# DC-DC_Isolation.net
KiCad netlist of a schematic drawn in Altium Designer
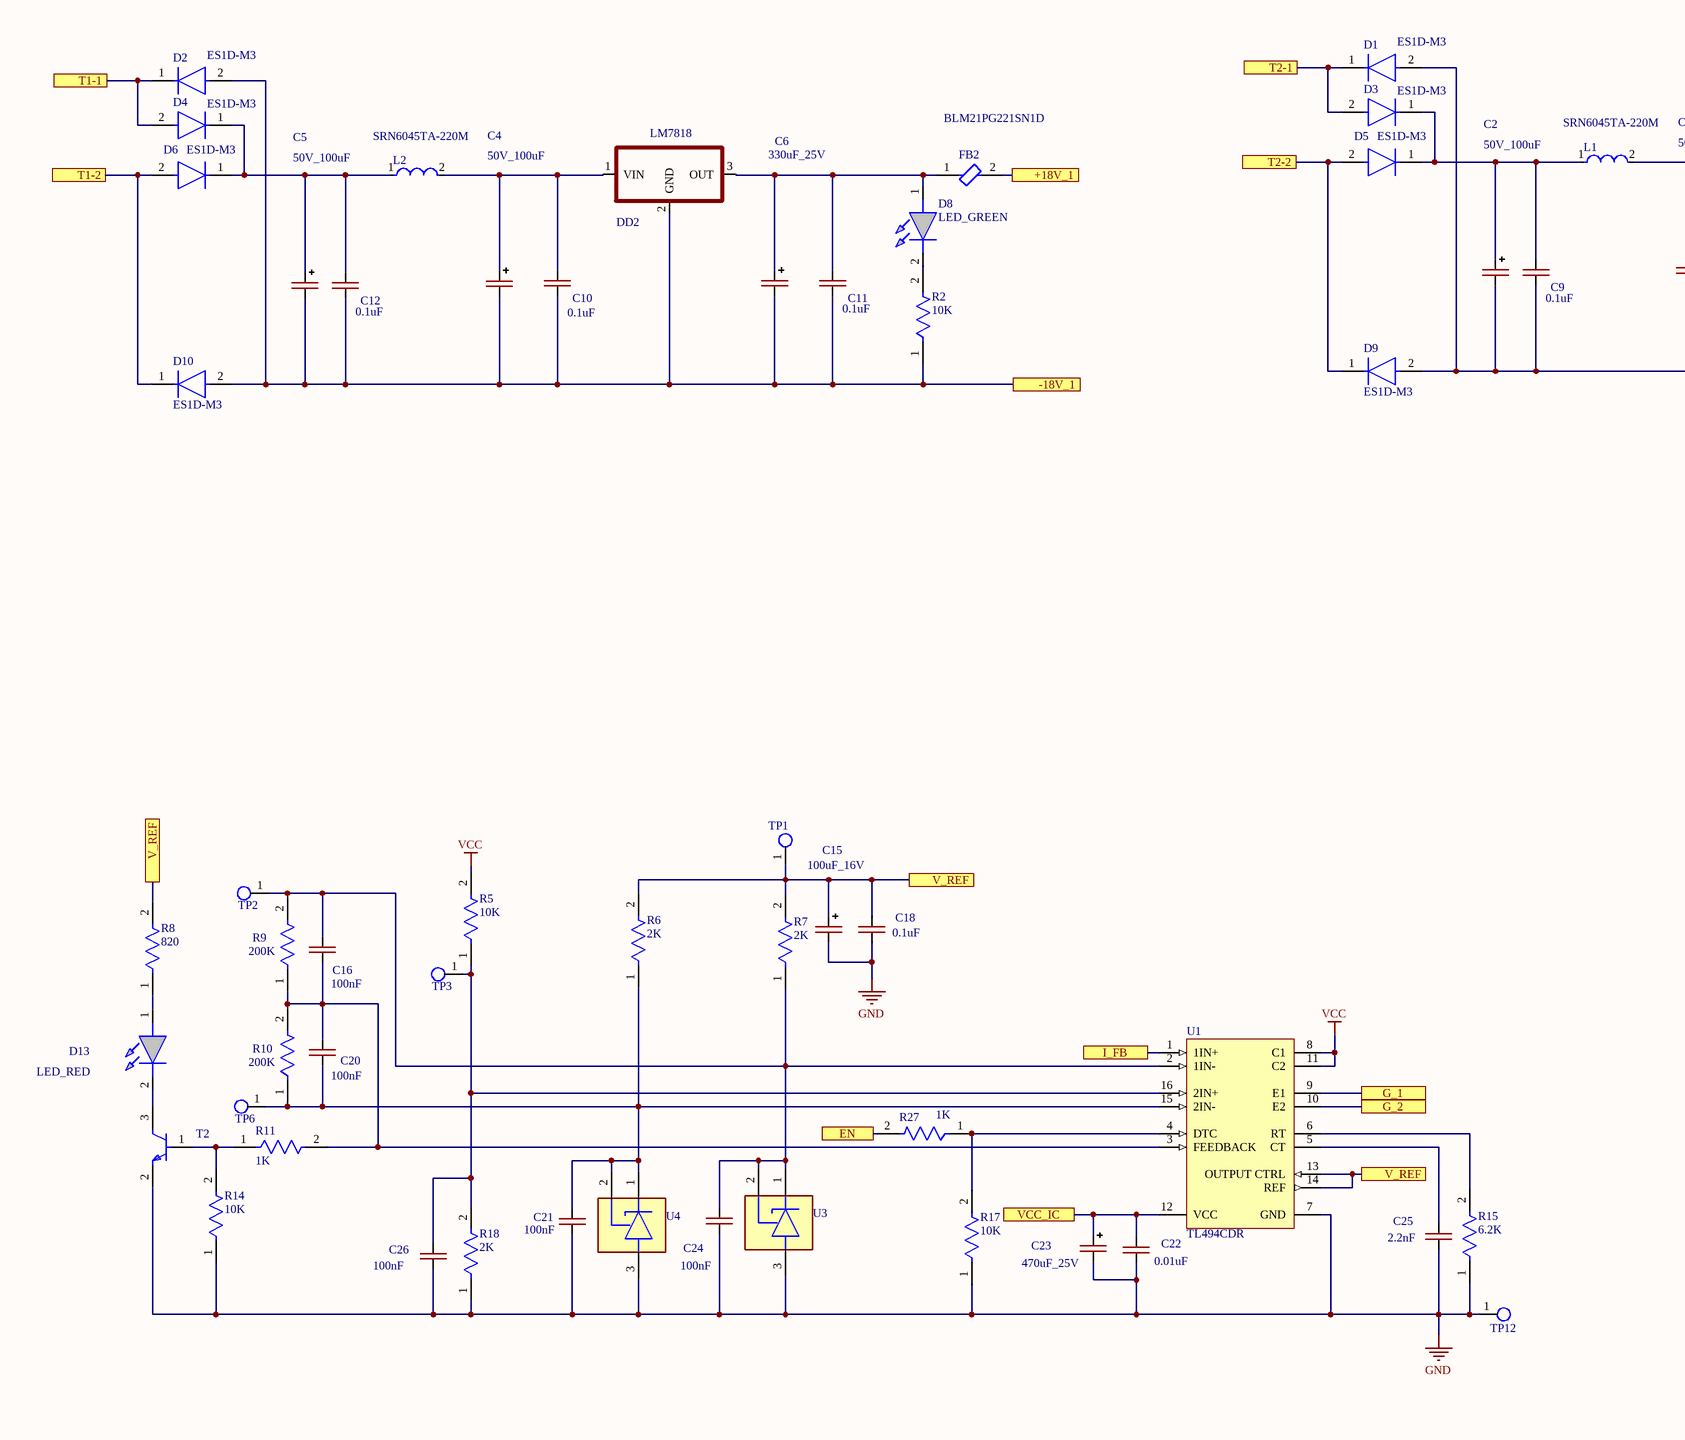
[diagram p0: DC-DC_Isolation.SchDoc, left]
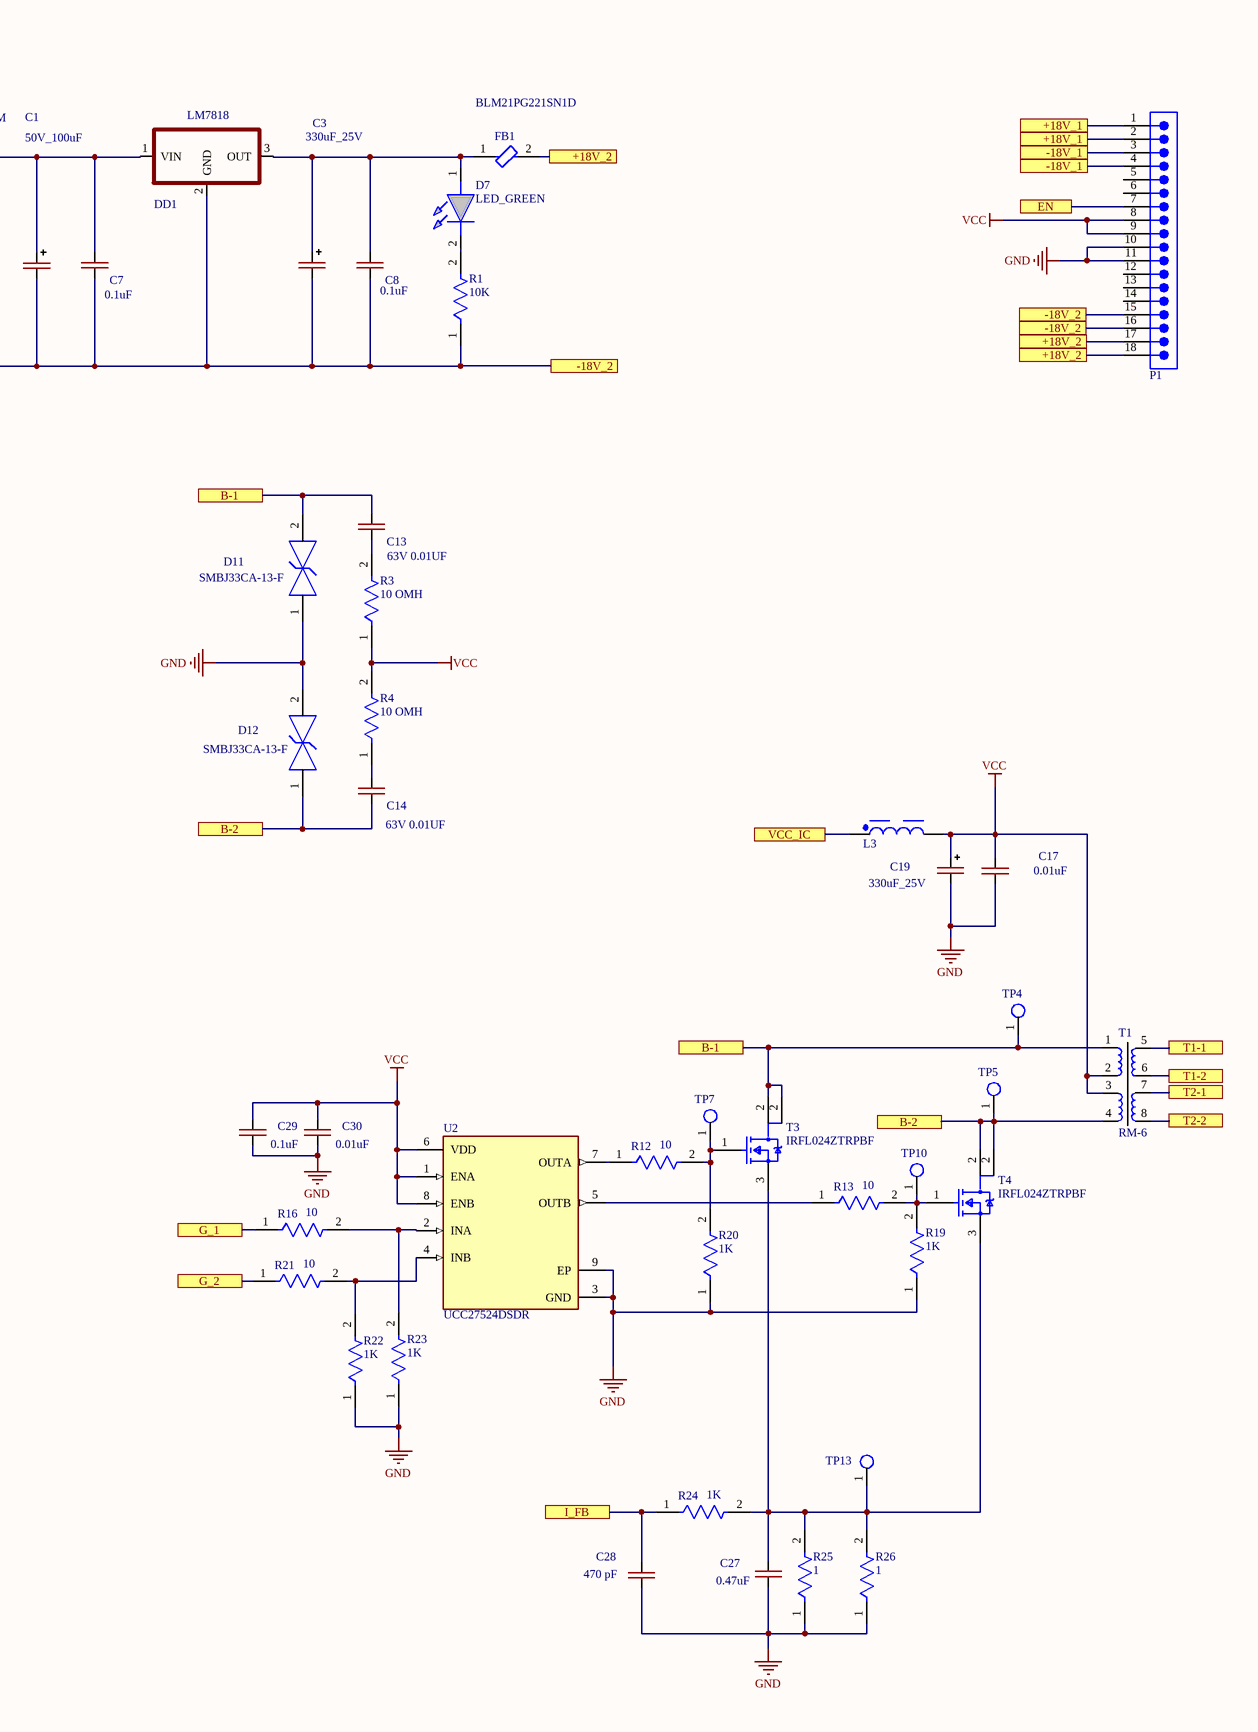
[diagram p1: DC-DC_Isolation.SchDoc, right]

(export (version "E")
  (design (tool "Eeschema 10.0.6"))
  (components
    (comp (ref "C1")
      (value "50V_100uF")
      (footprint "CAP_SMD_Size_G")
      (libsource (lib "PASSIVE_COMPONENTS") (part "CAP-POLAR"))
    )
    (comp (ref "C2")
      (value "50V_100uF")
      (footprint "CAP_SMD_Size_G")
      (libsource (lib "PASSIVE_COMPONENTS") (part "CAP-POLAR"))
    )
    (comp (ref "C3")
      (value "330uF_25V")
      (footprint "CAP_SMD_Size_G")
      (libsource (lib "PASSIVE_COMPONENTS") (part "CAP-POLAR"))
    )
    (comp (ref "C4")
      (value "50V_100uF")
      (footprint "CAP_SMD_Size_G")
      (libsource (lib "PASSIVE_COMPONENTS") (part "CAP-POLAR"))
    )
    (comp (ref "C5")
      (value "50V_100uF")
      (footprint "CAP_SMD_Size_G")
      (libsource (lib "PASSIVE_COMPONENTS") (part "CAP-POLAR"))
    )
    (comp (ref "C6")
      (value "330uF_25V")
      (footprint "CAP_SMD_Size_G")
      (libsource (lib "PASSIVE_COMPONENTS") (part "CAP-POLAR"))
    )
    (comp (ref "C7")
      (value "0.1uF")
      (footprint "CAP-0805")
      (description "0.1uF X7R")
      (libsource (lib "PASSIVE_COMPONENTS") (part "CAP-NON-POLAR"))
    )
    (comp (ref "C8")
      (value "0.1uF")
      (footprint "CAP-0805")
      (libsource (lib "PASSIVE_COMPONENTS") (part "CAP-NON-POLAR"))
    )
    (comp (ref "C9")
      (value "0.1uF")
      (footprint "CAP-0805")
      (description "0.1uF X7R")
      (libsource (lib "PASSIVE_COMPONENTS") (part "CAP-NON-POLAR"))
    )
    (comp (ref "C10")
      (value "0.1uF")
      (footprint "CAP-0805")
      (description "0.1uF X7R")
      (libsource (lib "PASSIVE_COMPONENTS") (part "CAP-NON-POLAR"))
    )
    (comp (ref "C11")
      (value "0.1uF")
      (footprint "CAP-0805")
      (libsource (lib "PASSIVE_COMPONENTS") (part "CAP-NON-POLAR"))
    )
    (comp (ref "C12")
      (value "0.1uF")
      (footprint "CAP-0805")
      (description "0.1uF X7R")
      (libsource (lib "PASSIVE_COMPONENTS") (part "CAP-NON-POLAR"))
    )
    (comp (ref "C13")
      (value "63V 0.01UF")
      (footprint "FKP2D011001A00JSSD")
      (description "WIMA Film Capacitor FKP2 63V 0.01UF")
      (libsource (lib "PASSIVE_COMPONENTS") (part "CAP-NON-POLAR"))
    )
    (comp (ref "C14")
      (value "63V 0.01UF")
      (footprint "FKP2D011001A00JSSD")
      (description "WIMA Film Capacitor FKP2 63V 0.01UF")
      (libsource (lib "PASSIVE_COMPONENTS") (part "CAP-NON-POLAR"))
    )
    (comp (ref "C15")
      (value "100uF_16V")
      (footprint "CAP-TAN-D")
      (libsource (lib "PASSIVE_COMPONENTS") (part "CAP-POLAR"))
    )
    (comp (ref "C16")
      (value "100nF")
      (footprint "CAP-0603")
      (libsource (lib "PASSIVE_COMPONENTS") (part "CAP-NON-POLAR"))
    )
    (comp (ref "C17")
      (value "0.01uF")
      (footprint "CAP-0805")
      (libsource (lib "PASSIVE_COMPONENTS") (part "CAP-NON-POLAR"))
    )
    (comp (ref "C18")
      (value "0.1uF")
      (footprint "CAP-0603")
      (libsource (lib "PASSIVE_COMPONENTS") (part "CAP-NON-POLAR"))
    )
    (comp (ref "C19")
      (value "330uF_25V")
      (footprint "CAP_SMD_Size_G")
      (libsource (lib "PASSIVE_COMPONENTS") (part "CAP-POLAR"))
    )
    (comp (ref "C20")
      (value "100nF")
      (footprint "CAP-0603")
      (libsource (lib "PASSIVE_COMPONENTS") (part "CAP-NON-POLAR"))
    )
    (comp (ref "C21")
      (value "100nF")
      (footprint "CAP-0603")
      (libsource (lib "PASSIVE_COMPONENTS") (part "CAP-NON-POLAR"))
    )
    (comp (ref "C22")
      (value "0.01uF")
      (footprint "CAP-0603")
      (libsource (lib "PASSIVE_COMPONENTS") (part "CAP-NON-POLAR"))
    )
    (comp (ref "C23")
      (value "470uF_25V")
      (footprint "CAP_SMD_Size_G")
      (libsource (lib "PASSIVE_COMPONENTS") (part "CAP-POLAR"))
    )
    (comp (ref "C24")
      (value "100nF")
      (footprint "CAP-0603")
      (libsource (lib "PASSIVE_COMPONENTS") (part "CAP-NON-POLAR"))
    )
    (comp (ref "C25")
      (value "2.2nF")
      (footprint "CAP-0603")
      (libsource (lib "PASSIVE_COMPONENTS") (part "CAP-NON-POLAR"))
    )
    (comp (ref "C26")
      (value "100nF")
      (footprint "CAP-0805")
      (libsource (lib "PASSIVE_COMPONENTS") (part "CAP-NON-POLAR"))
    )
    (comp (ref "C27")
      (value "0.47uF")
      (footprint "CAP-0603")
      (libsource (lib "PASSIVE_COMPONENTS") (part "CAP-NON-POLAR"))
    )
    (comp (ref "C28")
      (value "470 pF")
      (footprint "CAP-0603")
      (libsource (lib "PASSIVE_COMPONENTS") (part "CAP-NON-POLAR"))
    )
    (comp (ref "C29")
      (value "0.1uF")
      (footprint "CAP-0603")
      (libsource (lib "PASSIVE_COMPONENTS") (part "CAP-NON-POLAR"))
    )
    (comp (ref "C30")
      (value "0.01uF")
      (footprint "CAP-0603")
      (libsource (lib "PASSIVE_COMPONENTS") (part "CAP-NON-POLAR"))
    )
    (comp (ref "D1") (value "ES1D-M3") (footprint "FP-SMA-MFG") (libsource (lib "Diodes") (part "ES1D-M3")))
    (comp (ref "D2") (value "ES1D-M3") (footprint "FP-SMA-MFG") (libsource (lib "Diodes") (part "ES1D-M3")))
    (comp (ref "D3") (value "ES1D-M3") (footprint "FP-SMA-MFG") (libsource (lib "Diodes") (part "ES1D-M3")))
    (comp (ref "D4") (value "ES1D-M3") (footprint "FP-SMA-MFG") (libsource (lib "Diodes") (part "ES1D-M3")))
    (comp (ref "D5") (value "ES1D-M3") (footprint "FP-SMA-MFG") (libsource (lib "Diodes") (part "ES1D-M3")))
    (comp (ref "D6") (value "ES1D-M3") (footprint "FP-SMA-MFG") (libsource (lib "Diodes") (part "ES1D-M3")))
    (comp (ref "D7")
      (value "LED_GREEN")
      (footprint "LED_GREEN")
      (fields
        (field (name "MANUFACTURER_PART_NUMBER") "151031YS06000")
        (field (name "MOUSER PART NUMBER") "710-151031YS06000")
      )
      (libsource (lib "Optic-LED") (part "LED"))
    )
    (comp (ref "D8")
      (value "LED_GREEN")
      (footprint "LED_GREEN")
      (fields
        (field (name "MANUFACTURER_PART_NUMBER") "151031YS06000")
        (field (name "MOUSER PART NUMBER") "710-151031YS06000")
      )
      (libsource (lib "Optic-LED") (part "LED"))
    )
    (comp (ref "D9") (value "ES1D-M3") (footprint "FP-SMA-MFG") (libsource (lib "Diodes") (part "ES1D-M3")))
    (comp (ref "D10") (value "ES1D-M3") (footprint "FP-SMA-MFG") (libsource (lib "Diodes") (part "ES1D-M3")))
    (comp (ref "D11")
      (value "SMBJ33CA-13-F")
      (footprint "FP-SMB-CA-MFG")
      (description "TVS DIODE 33V 53.3V SMB")
      (libsource (lib "Diodes") (part "SMBJ33CA-13-F"))
    )
    (comp (ref "D12")
      (value "SMBJ33CA-13-F")
      (footprint "FP-SMB-CA-MFG")
      (description "TVS DIODE 33V 53.3V SMB")
      (libsource (lib "Diodes") (part "SMBJ33CA-13-F"))
    )
    (comp (ref "D13")
      (value "LED_RED")
      (footprint "LED_RED")
      (fields
        (field (name "MANUFACTURER_PART_NUMBER") "151031YS06000")
        (field (name "MOUSER PART NUMBER") "710-151031YS06000")
      )
      (libsource (lib "Optic-LED") (part "LED"))
    )
    (comp (ref "DD1")
      (value "LM7818")
      (footprint "TO-252")
      (libsource (lib "Integrated_Circuts") (part "LM7818"))
    )
    (comp (ref "DD2")
      (value "LM7818")
      (footprint "TO-252")
      (libsource (lib "Integrated_Circuts") (part "LM7818"))
    )
    (comp (ref "FB1")
      (value "BLM21PG221SN1D")
      (footprint "FP-BLM21-0_2-t0_85-e0_5-IPC_B")
      (description "Chip Ferrite Bead, 0805, 220Ω @ 100MHz, 0.045Ω, 25%, 2A")
      (fields (field (name "TOLERANCE") "25%"))
      (libsource (lib "Altium Content Vault") (part "5f30dd21d616792df468990f7003faa"))
    )
    (comp (ref "FB2")
      (value "BLM21PG221SN1D")
      (footprint "FP-BLM21-0_2-t0_85-e0_5-IPC_B")
      (description "Chip Ferrite Bead, 0805, 220Ω @ 100MHz, 0.045Ω, 25%, 2A")
      (fields (field (name "TOLERANCE") "25%"))
      (libsource (lib "Altium Content Vault") (part "5f30dd21d616792df468990f7003faa"))
    )
    (comp (ref "L1")
      (value "SRN6045TA-220M")
      (footprint "FP-SRN6045TA-MFG")
      (description "FIXED IND 22UH 2.3A 96 MOHM SMD")
      (libsource (lib "Altium Content Vault") (part "725321dda6339637d4d059423bc1c3c"))
    )
    (comp (ref "L2")
      (value "SRN6045TA-220M")
      (footprint "FP-SRN6045TA-MFG")
      (description "FIXED IND 22UH 2.3A 96 MOHM SMD")
      (libsource (lib "Altium Content Vault") (part "725321dda6339637d4d059423bc1c3c"))
    )
    (comp (ref "L3")
      (value "330µH, 0.38A")
      (footprint "WE-PD2_7850")
      (description "WE-PD2 SMT Power Inductor, size 7850, 390µH, 0.38A, 1.77Ω")
      (fields
        (field (name "MANUFACTURER PART NUMBER") "744775239")
        (field (name "MANUFACTURER") "Wurth Elektronik")
      )
      (libsource (lib "WE-PD2 (rev22d)") (part "744775239"))
    )
    (comp (ref "P1")
      (value "61301811021")
      (footprint "61301811021")
      (description "WR-PHD Pin Header, THT, Angled, pitch 2.54mm, 1 Row, 18P")
      (fields (field (name "MANUFACTURER") "Wurth Elektronik"))
      (libsource (lib "Altium_WR-PHD (rev24a)") (part "61301811021"))
    )
    (comp (ref "R1")
      (value "10K")
      (footprint "RES-0805")
      (libsource (lib "PASSIVE_COMPONENTS") (part "RES-CONST"))
    )
    (comp (ref "R2")
      (value "10K")
      (footprint "RES-0805")
      (libsource (lib "PASSIVE_COMPONENTS") (part "RES-CONST"))
    )
    (comp (ref "R3")
      (value "10 OMH")
      (footprint "RES-1206")
      (libsource (lib "PASSIVE_COMPONENTS") (part "RES-CONST"))
    )
    (comp (ref "R4")
      (value "10 OMH")
      (footprint "RES-1206")
      (libsource (lib "PASSIVE_COMPONENTS") (part "RES-CONST"))
    )
    (comp (ref "R5")
      (value "10K")
      (footprint "RES-0603")
      (libsource (lib "PASSIVE_COMPONENTS") (part "RES-CONST"))
    )
    (comp (ref "R6")
      (value "2K")
      (footprint "RES-0603")
      (libsource (lib "PASSIVE_COMPONENTS") (part "RES-CONST"))
    )
    (comp (ref "R7")
      (value "2K")
      (footprint "RES-0603")
      (libsource (lib "PASSIVE_COMPONENTS") (part "RES-CONST"))
    )
    (comp (ref "R8")
      (value "820")
      (footprint "RES-0603")
      (libsource (lib "PASSIVE_COMPONENTS") (part "RES-CONST"))
    )
    (comp (ref "R9")
      (value "200K")
      (footprint "RES-0603")
      (libsource (lib "PASSIVE_COMPONENTS") (part "RES-CONST"))
    )
    (comp (ref "R10")
      (value "200K")
      (footprint "RES-0603")
      (libsource (lib "PASSIVE_COMPONENTS") (part "RES-CONST"))
    )
    (comp (ref "R11")
      (value "1K")
      (footprint "RES-0603")
      (libsource (lib "PASSIVE_COMPONENTS") (part "RES-CONST"))
    )
    (comp (ref "R12")
      (value "10")
      (footprint "RES-0805")
      (libsource (lib "PASSIVE_COMPONENTS") (part "RES-CONST"))
    )
    (comp (ref "R13")
      (value "10")
      (footprint "RES-0805")
      (libsource (lib "PASSIVE_COMPONENTS") (part "RES-CONST"))
    )
    (comp (ref "R14")
      (value "10K")
      (footprint "RES-0603")
      (libsource (lib "PASSIVE_COMPONENTS") (part "RES-CONST"))
    )
    (comp (ref "R15")
      (value "6.2K")
      (footprint "RES-0603")
      (libsource (lib "PASSIVE_COMPONENTS") (part "RES-CONST"))
    )
    (comp (ref "R16")
      (value "10")
      (footprint "RES-0603")
      (libsource (lib "PASSIVE_COMPONENTS") (part "RES-CONST"))
    )
    (comp (ref "R17")
      (value "10K")
      (footprint "RES-0603")
      (libsource (lib "PASSIVE_COMPONENTS") (part "RES-CONST"))
    )
    (comp (ref "R18")
      (value "2K")
      (footprint "RES-0603")
      (libsource (lib "PASSIVE_COMPONENTS") (part "RES-CONST"))
    )
    (comp (ref "R19")
      (value "1K")
      (footprint "RES-0603")
      (libsource (lib "PASSIVE_COMPONENTS") (part "RES-CONST"))
    )
    (comp (ref "R20")
      (value "1K")
      (footprint "RES-0603")
      (libsource (lib "PASSIVE_COMPONENTS") (part "RES-CONST"))
    )
    (comp (ref "R21")
      (value "10")
      (footprint "RES-0603")
      (libsource (lib "PASSIVE_COMPONENTS") (part "RES-CONST"))
    )
    (comp (ref "R22")
      (value "1K")
      (footprint "RES-0603")
      (libsource (lib "PASSIVE_COMPONENTS") (part "RES-CONST"))
    )
    (comp (ref "R23")
      (value "1K")
      (footprint "RES-0603")
      (libsource (lib "PASSIVE_COMPONENTS") (part "RES-CONST"))
    )
    (comp (ref "R24")
      (value "1K")
      (footprint "RES-0603")
      (libsource (lib "PASSIVE_COMPONENTS") (part "RES-CONST"))
    )
    (comp (ref "R25")
      (value "1")
      (footprint "RES-2512")
      (libsource (lib "PASSIVE_COMPONENTS") (part "RES-CONST"))
    )
    (comp (ref "R26")
      (value "1")
      (footprint "RES-2512")
      (libsource (lib "PASSIVE_COMPONENTS") (part "RES-CONST"))
    )
    (comp (ref "R27")
      (value "1K")
      (footprint "RES-0603")
      (libsource (lib "PASSIVE_COMPONENTS") (part "RES-CONST"))
    )
    (comp (ref "T1")
      (value "RM-6")
      (footprint "TRANS_RM6")
      (libsource (lib "Transformers") (part "RM_6_12-12-18-18"))
    )
    (comp (ref "T2")
      (value "BC847C")
      (footprint "SOT23-3_IPC_A")
      (libsource (lib "Transistors") (part "BC847C"))
    )
    (comp (ref "T3")
      (value "IRFL024ZTRPBF")
      (footprint "SOT-223-3")
      (libsource (lib "Transistors") (part "IRFL024ZTRPBF"))
    )
    (comp (ref "T4")
      (value "IRFL024ZTRPBF")
      (footprint "SOT-223-3")
      (libsource (lib "Transistors") (part "IRFL024ZTRPBF"))
    )
    (comp (ref "TP1")
      (value "Test_Point_PCB")
      (footprint "Test_Point")
      (description "Test_Point")
      (libsource (lib "Test_Point") (part "TP_PCB?"))
    )
    (comp (ref "TP2")
      (value "Test_Point_PCB")
      (footprint "Test_Point")
      (description "Test_Point")
      (libsource (lib "Test_Point") (part "TP_PCB?"))
    )
    (comp (ref "TP3")
      (value "Test_Point_PCB")
      (footprint "Test_Point")
      (description "Test_Point")
      (libsource (lib "Test_Point") (part "TP_PCB?"))
    )
    (comp (ref "TP4")
      (value "~")
      (footprint "Test_Point")
      (description "Test_Point")
      (libsource (lib "Connectors") (part "TP_PCB?"))
    )
    (comp (ref "TP5")
      (value "~")
      (footprint "Test_Point")
      (description "Test_Point")
      (libsource (lib "Connectors") (part "TP_PCB?"))
    )
    (comp (ref "TP6")
      (value "~")
      (footprint "Test_Point")
      (description "Test_Point")
      (libsource (lib "Connectors") (part "TP_PCB?"))
    )
    (comp (ref "TP7")
      (value "~")
      (footprint "Test_Point")
      (description "Test_Point")
      (libsource (lib "Connectors") (part "TP_PCB?"))
    )
    (comp (ref "TP10")
      (value "~")
      (footprint "Test_Point")
      (description "Test_Point")
      (libsource (lib "Connectors") (part "TP_PCB?"))
    )
    (comp (ref "TP12")
      (value "~")
      (footprint "Test_Point")
      (description "Test_Point")
      (libsource (lib "Connectors") (part "TP_PCB?"))
    )
    (comp (ref "TP13")
      (value "~")
      (footprint "Test_Point")
      (description "Test_Point")
      (libsource (lib "Connectors") (part "TP_PCB?"))
    )
    (comp (ref "U1")
      (value "TL494CDR")
      (footprint "D0016A_N")
      (fields (field (name "MANUFACTURER") "Texas Instruments"))
      (libsource (lib "Altium Content Vault") (part "TI-494D16"))
    )
    (comp (ref "U2")
      (value "UCC27524DSDR")
      (footprint "FP-DSD0008D-IPC_A")
      (description "IC GATE DVR LO-SIDE DL 5A 8SON")
      (libsource (lib "Integrated_Circuts") (part "UCC27524DSDR"))
    )
    (comp (ref "U3")
      (value "TL431")
      (footprint "TL431_SOT-23-3(A)")
      (description "TL431_SOT-23-3")
      (libsource (lib "Diodes") (part "TL431_SOT-23-3"))
    )
    (comp (ref "U4")
      (value "TL431")
      (footprint "TL431_SOT-23-3(A)")
      (description "TL431_SOT-23-3")
      (libsource (lib "Diodes") (part "TL431_SOT-23-3"))
    )
  )
  (nets
    (net (code "1") (name "/+18V_1") (class "Default")
      (node (ref "FB2") (pin "2") (pinfunction "2_2") (pintype "passive"))
      (node (ref "P1") (pin "1") (pinfunction "1_1") (pintype "passive"))
      (node (ref "P1") (pin "2") (pinfunction "2_2") (pintype "passive"))
    )
    (net (code "2") (name "/+18V_2") (class "Default")
      (node (ref "FB1") (pin "2") (pinfunction "2_2") (pintype "passive"))
      (node (ref "P1") (pin "17") (pinfunction "17_17") (pintype "passive"))
      (node (ref "P1") (pin "18") (pinfunction "18_18") (pintype "passive"))
    )
    (net (code "3") (name "/-18V_1") (class "Default")
      (node (ref "C10") (pin "1") (pinfunction "1_1") (pintype "passive"))
      (node (ref "C11") (pin "1") (pinfunction "1_1") (pintype "passive"))
      (node (ref "C12") (pin "1") (pinfunction "1_1") (pintype "passive"))
      (node (ref "C4") (pin "2") (pinfunction "-_2") (pintype "passive"))
      (node (ref "C5") (pin "2") (pinfunction "-_2") (pintype "passive"))
      (node (ref "C6") (pin "2") (pinfunction "-_2") (pintype "passive"))
      (node (ref "D10") (pin "2") (pinfunction "A_2") (pintype "passive"))
      (node (ref "D2") (pin "2") (pinfunction "A_2") (pintype "passive"))
      (node (ref "DD2") (pin "2") (pinfunction "GND_2") (pintype "passive"))
      (node (ref "P1") (pin "3") (pinfunction "3_3") (pintype "passive"))
      (node (ref "P1") (pin "4") (pinfunction "4_4") (pintype "passive"))
      (node (ref "R2") (pin "1") (pinfunction "1_1") (pintype "passive"))
    )
    (net (code "4") (name "/-18V_2") (class "Default")
      (node (ref "C1") (pin "2") (pinfunction "-_2") (pintype "passive"))
      (node (ref "C2") (pin "2") (pinfunction "-_2") (pintype "passive"))
      (node (ref "C3") (pin "2") (pinfunction "-_2") (pintype "passive"))
      (node (ref "C7") (pin "1") (pinfunction "1_1") (pintype "passive"))
      (node (ref "C8") (pin "1") (pinfunction "1_1") (pintype "passive"))
      (node (ref "C9") (pin "1") (pinfunction "1_1") (pintype "passive"))
      (node (ref "D1") (pin "2") (pinfunction "A_2") (pintype "passive"))
      (node (ref "D9") (pin "2") (pinfunction "A_2") (pintype "passive"))
      (node (ref "DD1") (pin "2") (pinfunction "GND_2") (pintype "passive"))
      (node (ref "P1") (pin "15") (pinfunction "15_15") (pintype "passive"))
      (node (ref "P1") (pin "16") (pinfunction "16_16") (pintype "passive"))
      (node (ref "R1") (pin "1") (pinfunction "1_1") (pintype "passive"))
    )
    (net (code "5") (name "/B-1") (class "Default")
      (node (ref "C13") (pin "2") (pinfunction "2_2") (pintype "passive"))
      (node (ref "D11") (pin "2") (pinfunction "2_2") (pintype "passive"))
      (node (ref "T1") (pin "1") (pinfunction "1_1") (pintype "passive"))
      (node (ref "T3") (pin "2") (pinfunction "DRAIN_2") (pintype "passive"))
      (node (ref "TP4") (pin "1") (pinfunction "G9_1") (pintype "passive"))
    )
    (net (code "6") (name "/B-2") (class "Default")
      (node (ref "C14") (pin "2") (pinfunction "2_2") (pintype "passive"))
      (node (ref "D12") (pin "1") (pinfunction "1_1") (pintype "passive"))
      (node (ref "T1") (pin "4") (pinfunction "4_4") (pintype "passive"))
      (node (ref "T4") (pin "2") (pinfunction "DRAIN_2") (pintype "passive"))
      (node (ref "TP5") (pin "1") (pinfunction "G9_1") (pintype "passive"))
    )
    (net (code "7") (name "/EN") (class "Default")
      (node (ref "P1") (pin "7") (pinfunction "7_7") (pintype "passive"))
      (node (ref "R27") (pin "2") (pinfunction "2_2") (pintype "passive"))
    )
    (net (code "8") (name "/G_1") (class "Default")
      (node (ref "R16") (pin "1") (pinfunction "1_1") (pintype "passive"))
      (node (ref "U1") (pin "9") (pinfunction "E1_9") (pintype "passive"))
    )
    (net (code "9") (name "/G_2") (class "Default")
      (node (ref "R21") (pin "1") (pinfunction "1_1") (pintype "passive"))
      (node (ref "U1") (pin "10") (pinfunction "E2_10") (pintype "passive"))
    )
    (net (code "10") (name "/I_FB") (class "Default")
      (node (ref "C28") (pin "2") (pinfunction "2_2") (pintype "passive"))
      (node (ref "R24") (pin "1") (pinfunction "1_1") (pintype "passive"))
      (node (ref "U1") (pin "1") (pinfunction "1IN+_1") (pintype "input"))
    )
    (net (code "11") (name "/T1-1") (class "Default")
      (node (ref "D2") (pin "1") (pinfunction "C_1") (pintype "passive"))
      (node (ref "D4") (pin "2") (pinfunction "A_2") (pintype "passive"))
      (node (ref "T1") (pin "5") (pinfunction "5_5") (pintype "passive"))
    )
    (net (code "12") (name "/T1-2") (class "Default")
      (node (ref "D10") (pin "1") (pinfunction "C_1") (pintype "passive"))
      (node (ref "D6") (pin "2") (pinfunction "A_2") (pintype "passive"))
      (node (ref "T1") (pin "6") (pinfunction "6_6") (pintype "passive"))
    )
    (net (code "13") (name "/T2-1") (class "Default")
      (node (ref "D1") (pin "1") (pinfunction "C_1") (pintype "passive"))
      (node (ref "D3") (pin "2") (pinfunction "A_2") (pintype "passive"))
      (node (ref "T1") (pin "7") (pinfunction "7_7") (pintype "passive"))
    )
    (net (code "14") (name "/T2-2") (class "Default")
      (node (ref "D5") (pin "2") (pinfunction "A_2") (pintype "passive"))
      (node (ref "D9") (pin "1") (pinfunction "C_1") (pintype "passive"))
      (node (ref "T1") (pin "8") (pinfunction "8_8") (pintype "passive"))
    )
    (net (code "15") (name "/VCC_IC") (class "Default")
      (node (ref "C22") (pin "2") (pinfunction "2_2") (pintype "passive"))
      (node (ref "C23") (pin "1") (pinfunction "+_1") (pintype "passive"))
      (node (ref "L3") (pin "1") (pinfunction "1_1") (pintype "passive"))
      (node (ref "U1") (pin "12") (pinfunction "VCC_12") (pintype "power_in"))
    )
    (net (code "16") (name "/V_REF") (class "Default")
      (node (ref "C15") (pin "1") (pinfunction "+_1") (pintype "passive"))
      (node (ref "C18") (pin "2") (pinfunction "2_2") (pintype "passive"))
      (node (ref "R6") (pin "2") (pinfunction "2_2") (pintype "passive"))
      (node (ref "R7") (pin "2") (pinfunction "2_2") (pintype "passive"))
      (node (ref "R8") (pin "2") (pinfunction "2_2") (pintype "passive"))
      (node (ref "TP1") (pin "1") (pinfunction "G9_1") (pintype "passive"))
      (node (ref "U1") (pin "13") (pinfunction "OUTPUT_CTRL_13") (pintype "input"))
      (node (ref "U1") (pin "14") (pinfunction "REF_14") (pintype "output"))
    )
    (net (code "17") (name "GND") (class "Default")
      (node (ref "C15") (pin "2") (pinfunction "-_2") (pintype "passive"))
      (node (ref "C17") (pin "1") (pinfunction "1_1") (pintype "passive"))
      (node (ref "C18") (pin "1") (pinfunction "1_1") (pintype "passive"))
      (node (ref "C19") (pin "2") (pinfunction "-_2") (pintype "passive"))
      (node (ref "C21") (pin "1") (pinfunction "1_1") (pintype "passive"))
      (node (ref "C22") (pin "1") (pinfunction "1_1") (pintype "passive"))
      (node (ref "C23") (pin "2") (pinfunction "-_2") (pintype "passive"))
      (node (ref "C24") (pin "1") (pinfunction "1_1") (pintype "passive"))
      (node (ref "C25") (pin "1") (pinfunction "1_1") (pintype "passive"))
      (node (ref "C26") (pin "1") (pinfunction "1_1") (pintype "passive"))
      (node (ref "C27") (pin "1") (pinfunction "1_1") (pintype "passive"))
      (node (ref "C28") (pin "1") (pinfunction "1_1") (pintype "passive"))
      (node (ref "C29") (pin "1") (pinfunction "1_1") (pintype "passive"))
      (node (ref "C30") (pin "1") (pinfunction "1_1") (pintype "passive"))
      (node (ref "D11") (pin "1") (pinfunction "1_1") (pintype "passive"))
      (node (ref "D12") (pin "2") (pinfunction "2_2") (pintype "passive"))
      (node (ref "P1") (pin "10") (pinfunction "10_10") (pintype "passive"))
      (node (ref "P1") (pin "11") (pinfunction "11_11") (pintype "passive"))
      (node (ref "R14") (pin "1") (pinfunction "1_1") (pintype "passive"))
      (node (ref "R15") (pin "1") (pinfunction "1_1") (pintype "passive"))
      (node (ref "R17") (pin "1") (pinfunction "1_1") (pintype "passive"))
      (node (ref "R18") (pin "1") (pinfunction "1_1") (pintype "passive"))
      (node (ref "R19") (pin "1") (pinfunction "1_1") (pintype "passive"))
      (node (ref "R20") (pin "1") (pinfunction "1_1") (pintype "passive"))
      (node (ref "R22") (pin "1") (pinfunction "1_1") (pintype "passive"))
      (node (ref "R23") (pin "1") (pinfunction "1_1") (pintype "passive"))
      (node (ref "R25") (pin "1") (pinfunction "1_1") (pintype "passive"))
      (node (ref "R26") (pin "1") (pinfunction "1_1") (pintype "passive"))
      (node (ref "T2") (pin "2") (pinfunction "E_2") (pintype "passive"))
      (node (ref "TP12") (pin "1") (pinfunction "G9_1") (pintype "passive"))
      (node (ref "U1") (pin "7") (pinfunction "GND_7") (pintype "power_in"))
      (node (ref "U2") (pin "3") (pinfunction "GND_3") (pintype "power_in"))
      (node (ref "U2") (pin "9") (pinfunction "EP_9") (pintype "power_in"))
      (node (ref "U3") (pin "3") (pinfunction "A_3") (pintype "passive"))
      (node (ref "U4") (pin "3") (pinfunction "A_3") (pintype "passive"))
    )
    (net (code "18") (name "Net-(C1-+)") (class "Default")
      (node (ref "C1") (pin "1") (pinfunction "+_1") (pintype "passive"))
      (node (ref "C7") (pin "2") (pinfunction "2_2") (pintype "passive"))
      (node (ref "DD1") (pin "1") (pinfunction "VIN_1") (pintype "passive"))
      (node (ref "L1") (pin "2") (pinfunction "2_2") (pintype "passive"))
    )
    (net (code "19") (name "Net-(C2-+)") (class "Default")
      (node (ref "C2") (pin "1") (pinfunction "+_1") (pintype "passive"))
      (node (ref "C9") (pin "2") (pinfunction "2_2") (pintype "passive"))
      (node (ref "D3") (pin "1") (pinfunction "C_1") (pintype "passive"))
      (node (ref "D5") (pin "1") (pinfunction "C_1") (pintype "passive"))
      (node (ref "L1") (pin "1") (pinfunction "1_1") (pintype "passive"))
    )
    (net (code "20") (name "Net-(C3-+)") (class "Default")
      (node (ref "C3") (pin "1") (pinfunction "+_1") (pintype "passive"))
      (node (ref "C8") (pin "2") (pinfunction "2_2") (pintype "passive"))
      (node (ref "D7") (pin "1") (pinfunction "A_1") (pintype "passive"))
      (node (ref "DD1") (pin "3") (pinfunction "OUT_3") (pintype "passive"))
      (node (ref "FB1") (pin "1") (pinfunction "1_1") (pintype "passive"))
    )
    (net (code "21") (name "Net-(C4-+)") (class "Default")
      (node (ref "C10") (pin "2") (pinfunction "2_2") (pintype "passive"))
      (node (ref "C4") (pin "1") (pinfunction "+_1") (pintype "passive"))
      (node (ref "DD2") (pin "1") (pinfunction "VIN_1") (pintype "passive"))
      (node (ref "L2") (pin "2") (pinfunction "2_2") (pintype "passive"))
    )
    (net (code "22") (name "Net-(C5-+)") (class "Default")
      (node (ref "C12") (pin "2") (pinfunction "2_2") (pintype "passive"))
      (node (ref "C5") (pin "1") (pinfunction "+_1") (pintype "passive"))
      (node (ref "D4") (pin "1") (pinfunction "C_1") (pintype "passive"))
      (node (ref "D6") (pin "1") (pinfunction "C_1") (pintype "passive"))
      (node (ref "L2") (pin "1") (pinfunction "1_1") (pintype "passive"))
    )
    (net (code "23") (name "Net-(C6-+)") (class "Default")
      (node (ref "C11") (pin "2") (pinfunction "2_2") (pintype "passive"))
      (node (ref "C6") (pin "1") (pinfunction "+_1") (pintype "passive"))
      (node (ref "D8") (pin "1") (pinfunction "A_1") (pintype "passive"))
      (node (ref "DD2") (pin "3") (pinfunction "OUT_3") (pintype "passive"))
      (node (ref "FB2") (pin "1") (pinfunction "1_1") (pintype "passive"))
    )
    (net (code "24") (name "Net-(C13-Pad1)") (class "Default")
      (node (ref "C13") (pin "1") (pinfunction "1_1") (pintype "passive"))
      (node (ref "R3") (pin "2") (pinfunction "2_2") (pintype "passive"))
    )
    (net (code "25") (name "Net-(C14-Pad1)") (class "Default")
      (node (ref "C14") (pin "1") (pinfunction "1_1") (pintype "passive"))
      (node (ref "R4") (pin "1") (pinfunction "1_1") (pintype "passive"))
    )
    (net (code "26") (name "Net-(D7-K)") (class "Default")
      (node (ref "D7") (pin "2") (pinfunction "K_2") (pintype "passive"))
      (node (ref "R1") (pin "2") (pinfunction "2_2") (pintype "passive"))
    )
    (net (code "27") (name "Net-(D8-K)") (class "Default")
      (node (ref "D8") (pin "2") (pinfunction "K_2") (pintype "passive"))
      (node (ref "R2") (pin "2") (pinfunction "2_2") (pintype "passive"))
    )
    (net (code "28") (name "Net-(D13-A)") (class "Default")
      (node (ref "D13") (pin "1") (pinfunction "A_1") (pintype "passive"))
      (node (ref "R8") (pin "1") (pinfunction "1_1") (pintype "passive"))
    )
    (net (code "29") (name "Net-(D13-K)") (class "Default")
      (node (ref "D13") (pin "2") (pinfunction "K_2") (pintype "passive"))
      (node (ref "T2") (pin "3") (pinfunction "C_3") (pintype "passive"))
    )
    (net (code "30") (name "Net-(T2-B)") (class "Default")
      (node (ref "R11") (pin "1") (pinfunction "1_1") (pintype "passive"))
      (node (ref "R14") (pin "2") (pinfunction "2_2") (pintype "passive"))
      (node (ref "T2") (pin "1") (pinfunction "B_1") (pintype "passive"))
    )
    (net (code "31") (name "Net-(T3-GATE)") (class "Default")
      (node (ref "R12") (pin "2") (pinfunction "2_2") (pintype "passive"))
      (node (ref "R20") (pin "2") (pinfunction "2_2") (pintype "passive"))
      (node (ref "T3") (pin "1") (pinfunction "GATE_1") (pintype "passive"))
      (node (ref "TP7") (pin "1") (pinfunction "G9_1") (pintype "passive"))
    )
    (net (code "32") (name "Net-(T3-SOURCE)") (class "Default")
      (node (ref "C27") (pin "2") (pinfunction "2_2") (pintype "passive"))
      (node (ref "R24") (pin "2") (pinfunction "2_2") (pintype "passive"))
      (node (ref "R25") (pin "2") (pinfunction "2_2") (pintype "passive"))
      (node (ref "R26") (pin "2") (pinfunction "2_2") (pintype "passive"))
      (node (ref "T3") (pin "3") (pinfunction "SOURCE_3") (pintype "passive"))
      (node (ref "T4") (pin "3") (pinfunction "SOURCE_3") (pintype "passive"))
      (node (ref "TP13") (pin "1") (pinfunction "G9_1") (pintype "passive"))
    )
    (net (code "33") (name "Net-(T4-GATE)") (class "Default")
      (node (ref "R13") (pin "2") (pinfunction "2_2") (pintype "passive"))
      (node (ref "R19") (pin "2") (pinfunction "2_2") (pintype "passive"))
      (node (ref "T4") (pin "1") (pinfunction "GATE_1") (pintype "passive"))
      (node (ref "TP10") (pin "1") (pinfunction "G9_1") (pintype "passive"))
    )
    (net (code "34") (name "Net-(TP2-G9)") (class "Default")
      (node (ref "C16") (pin "2") (pinfunction "2_2") (pintype "passive"))
      (node (ref "C24") (pin "2") (pinfunction "2_2") (pintype "passive"))
      (node (ref "R7") (pin "1") (pinfunction "1_1") (pintype "passive"))
      (node (ref "R9") (pin "2") (pinfunction "2_2") (pintype "passive"))
      (node (ref "TP2") (pin "1") (pinfunction "G9_1") (pintype "passive"))
      (node (ref "U1") (pin "2") (pinfunction "1IN-_2") (pintype "input"))
      (node (ref "U3") (pin "1") (pinfunction "C_1") (pintype "passive"))
      (node (ref "U3") (pin "2") (pinfunction "REF_2") (pintype "passive"))
    )
    (net (code "35") (name "Net-(TP3-G9)") (class "Default")
      (node (ref "C26") (pin "2") (pinfunction "2_2") (pintype "passive"))
      (node (ref "R18") (pin "2") (pinfunction "2_2") (pintype "passive"))
      (node (ref "R5") (pin "1") (pinfunction "1_1") (pintype "passive"))
      (node (ref "TP3") (pin "1") (pinfunction "G9_1") (pintype "passive"))
      (node (ref "U1") (pin "16") (pinfunction "2IN+_16") (pintype "input"))
    )
    (net (code "36") (name "Net-(TP6-G9)") (class "Default")
      (node (ref "C20") (pin "1") (pinfunction "1_1") (pintype "passive"))
      (node (ref "C21") (pin "2") (pinfunction "2_2") (pintype "passive"))
      (node (ref "R10") (pin "1") (pinfunction "1_1") (pintype "passive"))
      (node (ref "R6") (pin "1") (pinfunction "1_1") (pintype "passive"))
      (node (ref "TP6") (pin "1") (pinfunction "G9_1") (pintype "passive"))
      (node (ref "U1") (pin "15") (pinfunction "2IN-_15") (pintype "input"))
      (node (ref "U4") (pin "1") (pinfunction "C_1") (pintype "passive"))
      (node (ref "U4") (pin "2") (pinfunction "REF_2") (pintype "passive"))
    )
    (net (code "37") (name "Net-(U1-CT)") (class "Default")
      (node (ref "C25") (pin "2") (pinfunction "2_2") (pintype "passive"))
      (node (ref "U1") (pin "5") (pinfunction "CT_5") (pintype "passive"))
    )
    (net (code "38") (name "Net-(U1-DTC)") (class "Default")
      (node (ref "R17") (pin "2") (pinfunction "2_2") (pintype "passive"))
      (node (ref "R27") (pin "1") (pinfunction "1_1") (pintype "passive"))
      (node (ref "U1") (pin "4") (pinfunction "DTC_4") (pintype "input"))
    )
    (net (code "39") (name "Net-(U1-FEEDBACK)") (class "Default")
      (node (ref "C16") (pin "1") (pinfunction "1_1") (pintype "passive"))
      (node (ref "C20") (pin "2") (pinfunction "2_2") (pintype "passive"))
      (node (ref "R10") (pin "2") (pinfunction "2_2") (pintype "passive"))
      (node (ref "R11") (pin "2") (pinfunction "2_2") (pintype "passive"))
      (node (ref "R9") (pin "1") (pinfunction "1_1") (pintype "passive"))
      (node (ref "U1") (pin "3") (pinfunction "FEEDBACK_3") (pintype "input"))
    )
    (net (code "40") (name "Net-(U1-RT)") (class "Default")
      (node (ref "R15") (pin "2") (pinfunction "2_2") (pintype "passive"))
      (node (ref "U1") (pin "6") (pinfunction "RT_6") (pintype "passive"))
    )
    (net (code "41") (name "Net-(U2-INA)") (class "Default")
      (node (ref "R16") (pin "2") (pinfunction "2_2") (pintype "passive"))
      (node (ref "R23") (pin "2") (pinfunction "2_2") (pintype "passive"))
      (node (ref "U2") (pin "2") (pinfunction "INA_2") (pintype "input"))
    )
    (net (code "42") (name "Net-(U2-INB)") (class "Default")
      (node (ref "R21") (pin "2") (pinfunction "2_2") (pintype "passive"))
      (node (ref "R22") (pin "2") (pinfunction "2_2") (pintype "passive"))
      (node (ref "U2") (pin "4") (pinfunction "INB_4") (pintype "input"))
    )
    (net (code "43") (name "Net-(U2-OUTA)") (class "Default")
      (node (ref "R12") (pin "1") (pinfunction "1_1") (pintype "passive"))
      (node (ref "U2") (pin "7") (pinfunction "OUTA_7") (pintype "output"))
    )
    (net (code "44") (name "Net-(U2-OUTB)") (class "Default")
      (node (ref "R13") (pin "1") (pinfunction "1_1") (pintype "passive"))
      (node (ref "U2") (pin "5") (pinfunction "OUTB_5") (pintype "output"))
    )
    (net (code "45") (name "VCC") (class "Default")
      (node (ref "C17") (pin "2") (pinfunction "2_2") (pintype "passive"))
      (node (ref "C19") (pin "1") (pinfunction "+_1") (pintype "passive"))
      (node (ref "C29") (pin "2") (pinfunction "2_2") (pintype "passive"))
      (node (ref "C30") (pin "2") (pinfunction "2_2") (pintype "passive"))
      (node (ref "L3") (pin "2") (pinfunction "2_2") (pintype "passive"))
      (node (ref "P1") (pin "8") (pinfunction "8_8") (pintype "passive"))
      (node (ref "P1") (pin "9") (pinfunction "9_9") (pintype "passive"))
      (node (ref "R3") (pin "1") (pinfunction "1_1") (pintype "passive"))
      (node (ref "R4") (pin "2") (pinfunction "2_2") (pintype "passive"))
      (node (ref "R5") (pin "2") (pinfunction "2_2") (pintype "passive"))
      (node (ref "T1") (pin "2") (pinfunction "2_2") (pintype "passive"))
      (node (ref "T1") (pin "3") (pinfunction "3_3") (pintype "passive"))
      (node (ref "U1") (pin "11") (pinfunction "C2_11") (pintype "passive"))
      (node (ref "U1") (pin "8") (pinfunction "C1_8") (pintype "passive"))
      (node (ref "U2") (pin "1") (pinfunction "ENA_1") (pintype "input"))
      (node (ref "U2") (pin "6") (pinfunction "VDD_6") (pintype "power_in"))
      (node (ref "U2") (pin "8") (pinfunction "ENB_8") (pintype "input"))
    )
    (net (code "46") (name "unconnected-(P1-Pad5)") (class "Default")
      (node (ref "P1") (pin "5") (pinfunction "5_5") (pintype "passive"))
    )
    (net (code "47") (name "unconnected-(P1-Pad6)") (class "Default")
      (node (ref "P1") (pin "6") (pinfunction "6_6") (pintype "passive"))
    )
    (net (code "48") (name "unconnected-(P1-Pad12)") (class "Default")
      (node (ref "P1") (pin "12") (pinfunction "12_12") (pintype "passive"))
    )
    (net (code "49") (name "unconnected-(P1-Pad13)") (class "Default")
      (node (ref "P1") (pin "13") (pinfunction "13_13") (pintype "passive"))
    )
    (net (code "50") (name "unconnected-(P1-Pad14)") (class "Default")
      (node (ref "P1") (pin "14") (pinfunction "14_14") (pintype "passive"))
    )
  )
)
